# DoorchimeCR2.net
KiCad netlist of a schematic drawn in EAGLE
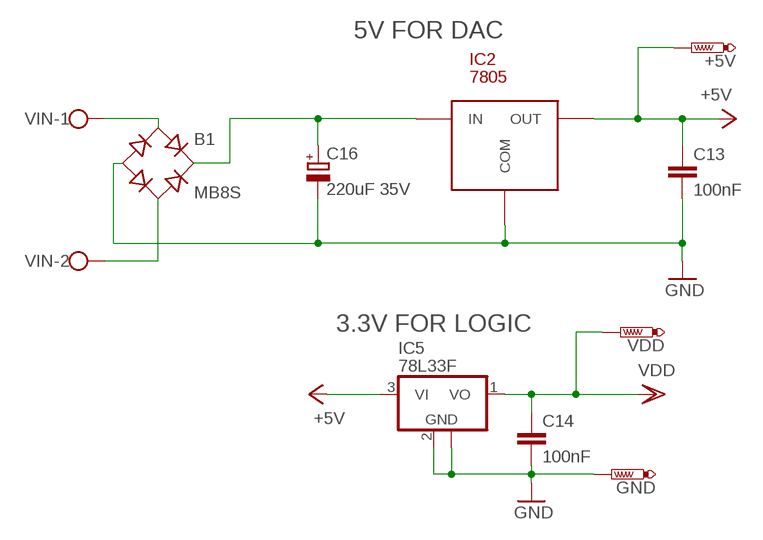
[diagram p0: schematic, sheet 1]
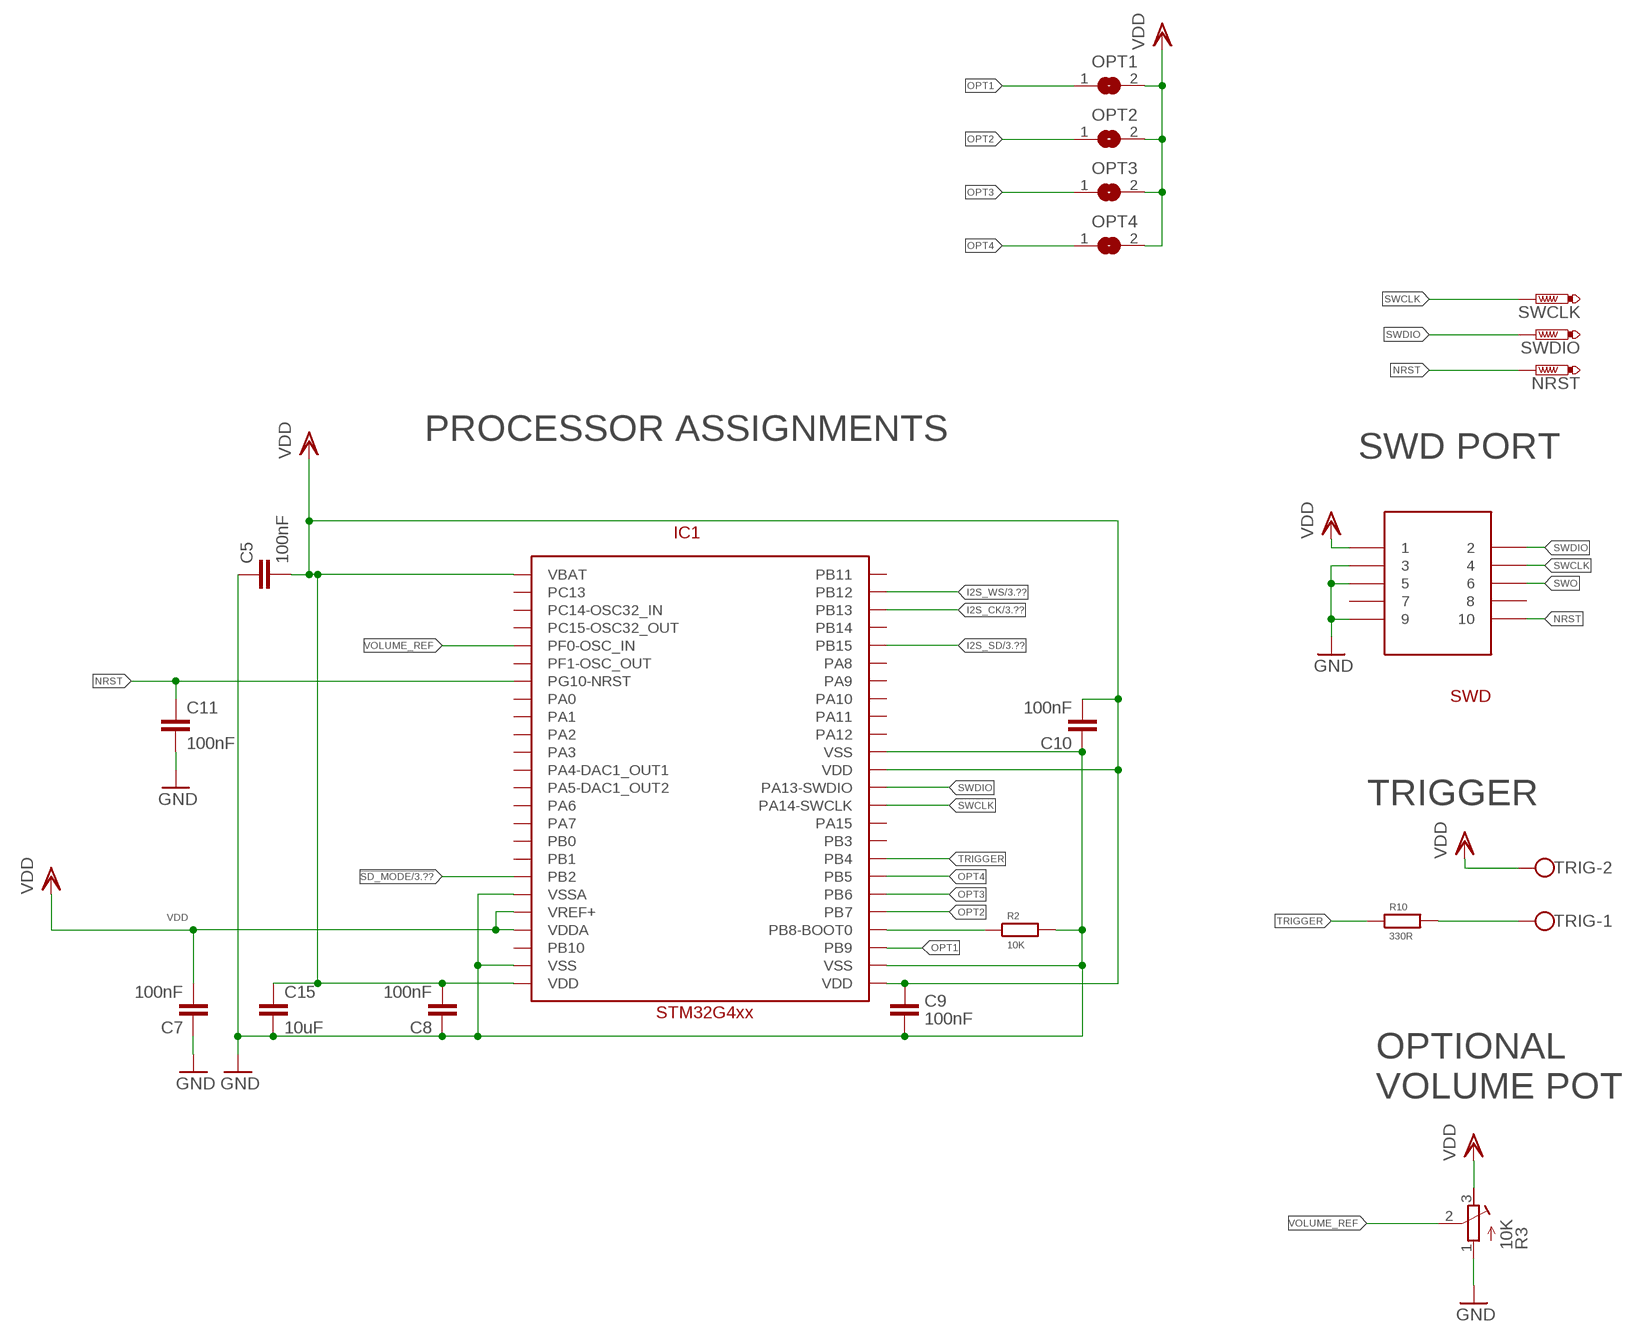
[diagram p1: schematic, sheet 2]
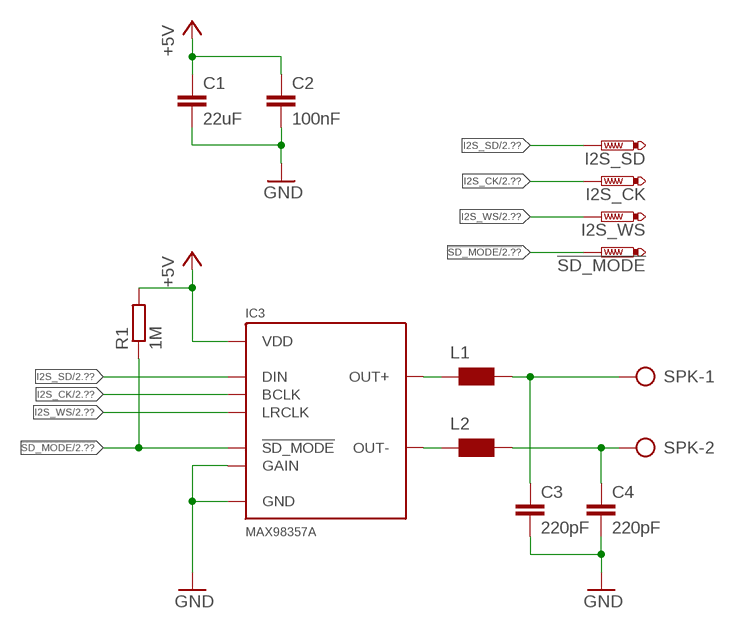
[diagram p2: schematic, sheet 3]

(export (version "E")
  (design (tool "Eeschema 10.0.6"))
  (components
    (comp (ref "+5V")
      (value "PTR1TP15R")
      (footprint "eagle-import:TP15R")
      (libsource (lib "eagle-import") (part "PTR1TP15R"))
    )
    (comp (ref "B1")
      (value "MB8S")
      (footprint "eagle-import:SOIC-4")
      (libsource (lib "eagle-import") (part "MBS8"))
    )
    (comp (ref "C13")
      (value "100nF")
      (footprint "eagle-import:C0603")
      (libsource (lib "eagle-import") (part "C-EUC0603"))
    )
    (comp (ref "C14")
      (value "100nF")
      (footprint "eagle-import:C0603")
      (libsource (lib "eagle-import") (part "C-EUC0603"))
    )
    (comp (ref "C16")
      (value "220uF 35V")
      (footprint "eagle-import:153CLV-0807")
      (libsource (lib "eagle-import") (part "CPOL-EU153CLV-0807"))
    )
    (comp (ref "GND")
      (value "PTR1TP15R")
      (footprint "eagle-import:TP15R")
      (libsource (lib "eagle-import") (part "PTR1TP15R"))
    )
    (comp (ref "IC2")
      (value "7805")
      (footprint "eagle-import:D2PAK")
      (libsource (lib "eagle-import") (part "78XX-D2PAK"))
    )
    (comp (ref "IC5")
      (value "78L33F")
      (footprint "eagle-import:SOT89")
      (libsource (lib "eagle-import") (part "78LF05"))
    )
    (comp (ref "VDD")
      (value "PTR1TP15R")
      (footprint "eagle-import:TP15R")
      (libsource (lib "eagle-import") (part "PTR1TP15R"))
    )
    (comp (ref "VIN")
      (value "W237-102")
      (footprint "eagle-import:W237-102")
      (fields (field (name "MPN") "237-102"))
      (libsource (lib "eagle-import") (part "W237-102"))
    )
    (comp (ref "C5")
      (value "100nF")
      (footprint "eagle-import:C0603")
      (libsource (lib "eagle-import") (part "C-EUC0603"))
    )
    (comp (ref "C7")
      (value "100nF")
      (footprint "eagle-import:C0603")
      (libsource (lib "eagle-import") (part "C-EUC0603"))
    )
    (comp (ref "C8")
      (value "100nF")
      (footprint "eagle-import:C0603")
      (libsource (lib "eagle-import") (part "C-EUC0603"))
    )
    (comp (ref "C9")
      (value "100nF")
      (footprint "eagle-import:C0603")
      (libsource (lib "eagle-import") (part "C-EUC0603"))
    )
    (comp (ref "C10")
      (value "100nF")
      (footprint "eagle-import:C0603")
      (libsource (lib "eagle-import") (part "C-EUC0603"))
    )
    (comp (ref "C11")
      (value "100nF")
      (footprint "eagle-import:C0603")
      (libsource (lib "eagle-import") (part "C-EUC0603"))
    )
    (comp (ref "C15")
      (value "10uF")
      (footprint "eagle-import:C0603")
      (libsource (lib "eagle-import") (part "C-EUC0603"))
    )
    (comp (ref "IC1")
      (value "STM32G4xx")
      (footprint "eagle-import:TQFP48")
      (libsource (lib "eagle-import") (part "STM32G431-C8T6"))
    )
    (comp (ref "NRST")
      (value "PTR1TP15R")
      (footprint "eagle-import:TP15R")
      (libsource (lib "eagle-import") (part "PTR1TP15R"))
    )
    (comp (ref "OPT1")
      (value "SJ")
      (footprint "eagle-import:SJ")
      (libsource (lib "eagle-import") (part "SJ"))
    )
    (comp (ref "OPT2")
      (value "SJ")
      (footprint "eagle-import:SJ")
      (libsource (lib "eagle-import") (part "SJ"))
    )
    (comp (ref "OPT3")
      (value "SJ")
      (footprint "eagle-import:SJ")
      (libsource (lib "eagle-import") (part "SJ"))
    )
    (comp (ref "OPT4")
      (value "SJ")
      (footprint "eagle-import:SJ")
      (libsource (lib "eagle-import") (part "SJ"))
    )
    (comp (ref "R2")
      (value "10K")
      (footprint "eagle-import:R0603")
      (libsource (lib "eagle-import") (part "R-EU_R0603"))
    )
    (comp (ref "R3")
      (value "10K")
      (footprint "eagle-import:RTRIM3339P")
      (libsource (lib "eagle-import") (part "R-TRIMM3339P"))
    )
    (comp (ref "R10")
      (value "330R")
      (footprint "eagle-import:R0603")
      (libsource (lib "eagle-import") (part "R-EU_R0603"))
    )
    (comp (ref "SWCLK")
      (value "PTR1TP15R")
      (footprint "eagle-import:TP15R")
      (libsource (lib "eagle-import") (part "PTR1TP15R"))
    )
    (comp (ref "SWD")
      (value "FTSH-105-01")
      (footprint "eagle-import:FTSH-105-01-XXX-DV-K")
      (libsource (lib "eagle-import") (part "FTSH-105-01"))
    )
    (comp (ref "SWDIO")
      (value "PTR1TP15R")
      (footprint "eagle-import:TP15R")
      (libsource (lib "eagle-import") (part "PTR1TP15R"))
    )
    (comp (ref "TRIG")
      (value "W237-102")
      (footprint "eagle-import:W237-102")
      (fields (field (name "MPN") "237-102"))
      (libsource (lib "eagle-import") (part "W237-102"))
    )
    (comp (ref "!SD_MODE")
      (value "PTR1TP15R")
      (footprint "eagle-import:TP15R")
      (libsource (lib "eagle-import") (part "PTR1TP15R"))
    )
    (comp (ref "C1")
      (value "22uF")
      (footprint "eagle-import:C0603")
      (libsource (lib "eagle-import") (part "C-EUC0603"))
    )
    (comp (ref "C2")
      (value "100nF")
      (footprint "eagle-import:C0603")
      (libsource (lib "eagle-import") (part "C-EUC0603"))
    )
    (comp (ref "C3")
      (value "220pF")
      (footprint "eagle-import:C0603")
      (libsource (lib "eagle-import") (part "C-EUC0603"))
    )
    (comp (ref "C4")
      (value "220pF")
      (footprint "eagle-import:C0603")
      (libsource (lib "eagle-import") (part "C-EUC0603"))
    )
    (comp (ref "I2S_CK")
      (value "PTR1TP15R")
      (footprint "eagle-import:TP15R")
      (libsource (lib "eagle-import") (part "PTR1TP15R"))
    )
    (comp (ref "I2S_SD")
      (value "PTR1TP15R")
      (footprint "eagle-import:TP15R")
      (libsource (lib "eagle-import") (part "PTR1TP15R"))
    )
    (comp (ref "I2S_WS")
      (value "PTR1TP15R")
      (footprint "eagle-import:TP15R")
      (libsource (lib "eagle-import") (part "PTR1TP15R"))
    )
    (comp (ref "IC3")
      (value "MAX98357A")
      (footprint "eagle-import:TQFN-16")
      (libsource (lib "eagle-import") (part "MAX98357A"))
    )
    (comp (ref "L1")
      (value "WE-CBF_0603")
      (footprint "eagle-import:0603")
      (libsource (lib "eagle-import") (part "WE-CBF_0603"))
    )
    (comp (ref "L2")
      (value "WE-CBF_0603")
      (footprint "eagle-import:0603")
      (libsource (lib "eagle-import") (part "WE-CBF_0603"))
    )
    (comp (ref "R1")
      (value "1M")
      (footprint "eagle-import:R0603")
      (libsource (lib "eagle-import") (part "R-EU_R0603"))
    )
    (comp (ref "SPK")
      (value "W237-102")
      (footprint "eagle-import:W237-102")
      (fields (field (name "MPN") "237-102"))
      (libsource (lib "eagle-import") (part "W237-102"))
    )
  )
  (nets
    (net (code "1") (name "+5V") (class "Default")
      (node (ref "+5V") (pin "TP") (pinfunction "TP_TP") (pintype "input"))
      (node (ref "C1") (pin "1") (pinfunction "1_1") (pintype "passive"))
      (node (ref "C13") (pin "1") (pinfunction "1_1") (pintype "passive"))
      (node (ref "C2") (pin "1") (pinfunction "1_1") (pintype "passive"))
      (node (ref "IC2") (pin "OUT") (pinfunction "OUT_OUT") (pintype "bidirectional"))
      (node (ref "IC3") (pin "P$7") (pinfunction "VDD_P$7") (pintype "bidirectional"))
      (node (ref "IC3") (pin "P$8") (pinfunction "VDD_P$8") (pintype "bidirectional"))
      (node (ref "IC5") (pin "3") (pinfunction "VI_3") (pintype "input"))
      (node (ref "R1") (pin "2") (pinfunction "2_2") (pintype "passive"))
    )
    (net (code "2") (name "GND") (class "Default")
      (node (ref "B1") (pin "-") (pinfunction "-_-") (pintype "passive"))
      (node (ref "C1") (pin "2") (pinfunction "2_2") (pintype "passive"))
      (node (ref "C10") (pin "1") (pinfunction "1_1") (pintype "passive"))
      (node (ref "C11") (pin "2") (pinfunction "2_2") (pintype "passive"))
      (node (ref "C13") (pin "2") (pinfunction "2_2") (pintype "passive"))
      (node (ref "C14") (pin "2") (pinfunction "2_2") (pintype "passive"))
      (node (ref "C15") (pin "2") (pinfunction "2_2") (pintype "passive"))
      (node (ref "C16") (pin "-") (pinfunction "-_-") (pintype "passive"))
      (node (ref "C2") (pin "2") (pinfunction "2_2") (pintype "passive"))
      (node (ref "C3") (pin "2") (pinfunction "2_2") (pintype "passive"))
      (node (ref "C4") (pin "2") (pinfunction "2_2") (pintype "passive"))
      (node (ref "C5") (pin "1") (pinfunction "1_1") (pintype "passive"))
      (node (ref "C7") (pin "1") (pinfunction "1_1") (pintype "passive"))
      (node (ref "C8") (pin "1") (pinfunction "1_1") (pintype "passive"))
      (node (ref "C9") (pin "1") (pinfunction "1_1") (pintype "passive"))
      (node (ref "GND") (pin "TP") (pinfunction "TP_TP") (pintype "input"))
      (node (ref "IC1") (pin "VSS@23") (pinfunction "VSS_VSS@23") (pintype "power_in"))
      (node (ref "IC1") (pin "VSS@35") (pinfunction "VSS_VSS@35") (pintype "power_in"))
      (node (ref "IC1") (pin "VSS@47") (pinfunction "VSS_VSS@47") (pintype "power_in"))
      (node (ref "IC1") (pin "VSSA") (pinfunction "VSSA_VSSA") (pintype "power_in"))
      (node (ref "IC2") (pin "COM") (pinfunction "COM_COM") (pintype "bidirectional"))
      (node (ref "IC3") (pin "P$11") (pinfunction "GND_P$11") (pintype "bidirectional"))
      (node (ref "IC3") (pin "P$15") (pinfunction "GND_P$15") (pintype "bidirectional"))
      (node (ref "IC3") (pin "P$2") (pinfunction "GAIN_P$2") (pintype "bidirectional"))
      (node (ref "IC3") (pin "P$3") (pinfunction "GND_P$3") (pintype "bidirectional"))
      (node (ref "IC3") (pin "P$EP") (pinfunction "GND_P$EP") (pintype "bidirectional"))
      (node (ref "IC5") (pin "2") (pinfunction "GND_2") (pintype "passive"))
      (node (ref "IC5") (pin "2@1") (pinfunction "GND_2@1") (pintype "passive"))
      (node (ref "R2") (pin "2") (pinfunction "2_2") (pintype "passive"))
      (node (ref "R3") (pin "1") (pinfunction "E_1") (pintype "passive"))
      (node (ref "SWD") (pin "3") (pinfunction "3_3") (pintype "passive"))
      (node (ref "SWD") (pin "5") (pinfunction "5_5") (pintype "passive"))
      (node (ref "SWD") (pin "9") (pinfunction "9_9") (pintype "passive"))
    )
    (net (code "3") (name "I2S_CK") (class "Default")
      (node (ref "I2S_CK") (pin "TP") (pinfunction "TP_TP") (pintype "input"))
      (node (ref "IC1") (pin "PB13") (pinfunction "PB13_PB13") (pintype "bidirectional"))
      (node (ref "IC3") (pin "P$16") (pinfunction "BCLK_P$16") (pintype "bidirectional"))
    )
    (net (code "4") (name "I2S_SD") (class "Default")
      (node (ref "I2S_SD") (pin "TP") (pinfunction "TP_TP") (pintype "input"))
      (node (ref "IC1") (pin "PB15") (pinfunction "PB15_PB15") (pintype "bidirectional"))
      (node (ref "IC3") (pin "P$1") (pinfunction "DIN_P$1") (pintype "bidirectional"))
    )
    (net (code "5") (name "I2S_WS") (class "Default")
      (node (ref "I2S_WS") (pin "TP") (pinfunction "TP_TP") (pintype "input"))
      (node (ref "IC1") (pin "PB12") (pinfunction "PB12_PB12") (pintype "bidirectional"))
      (node (ref "IC3") (pin "P$14") (pinfunction "LRCLK_P$14") (pintype "bidirectional"))
    )
    (net (code "6") (name "NRST") (class "Default")
      (node (ref "C11") (pin "1") (pinfunction "1_1") (pintype "passive"))
      (node (ref "IC1") (pin "PG10-NRST") (pinfunction "PG10-NRST_PG10-NRST") (pintype "bidirectional"))
      (node (ref "NRST") (pin "TP") (pinfunction "TP_TP") (pintype "input"))
      (node (ref "SWD") (pin "10") (pinfunction "10_10") (pintype "passive"))
    )
    (net (code "7") (name "Net-(B1-AC1)") (class "Default")
      (node (ref "B1") (pin "~1") (pinfunction "AC1_~1") (pintype "passive"))
      (node (ref "VIN") (pin "1") (pinfunction "KL_1") (pintype "passive"))
    )
    (net (code "8") (name "Net-(B1-AC2)") (class "Default")
      (node (ref "B1") (pin "~2") (pinfunction "AC2_~2") (pintype "passive"))
      (node (ref "VIN") (pin "2") (pinfunction "KL_2") (pintype "passive"))
    )
    (net (code "9") (name "Net-(B1-Pad+)") (class "Default")
      (node (ref "B1") (pin "+") (pinfunction "+_+") (pintype "passive"))
      (node (ref "C16") (pin "+") (pinfunction "+_+") (pintype "passive"))
      (node (ref "IC2") (pin "IN") (pinfunction "IN_IN") (pintype "bidirectional"))
    )
    (net (code "10") (name "Net-(IC1-PadPB8-BOOT0)") (class "Default")
      (node (ref "IC1") (pin "PB8-BOOT0") (pinfunction "PB8-BOOT0_PB8-BOOT0") (pintype "bidirectional"))
      (node (ref "R2") (pin "1") (pinfunction "1_1") (pintype "passive"))
    )
    (net (code "11") (name "Net-(IC3-OUT+)") (class "Default")
      (node (ref "IC3") (pin "P$9") (pinfunction "OUT+_P$9") (pintype "bidirectional"))
      (node (ref "L1") (pin "1") (pinfunction "1_1") (pintype "passive"))
    )
    (net (code "12") (name "Net-(IC3-OUT-)") (class "Default")
      (node (ref "IC3") (pin "P$10") (pinfunction "OUT-_P$10") (pintype "bidirectional"))
      (node (ref "L2") (pin "1") (pinfunction "1_1") (pintype "passive"))
    )
    (net (code "13") (name "Net-(SPKA-KL)") (class "Default")
      (node (ref "C3") (pin "1") (pinfunction "1_1") (pintype "passive"))
      (node (ref "L1") (pin "2") (pinfunction "2_2") (pintype "passive"))
      (node (ref "SPK") (pin "1") (pinfunction "KL_1") (pintype "passive"))
    )
    (net (code "14") (name "Net-(SPKB-KL)") (class "Default")
      (node (ref "C4") (pin "1") (pinfunction "1_1") (pintype "passive"))
      (node (ref "L2") (pin "2") (pinfunction "2_2") (pintype "passive"))
      (node (ref "SPK") (pin "2") (pinfunction "KL_2") (pintype "passive"))
    )
    (net (code "15") (name "Net-(TRIGA-KL)") (class "Default")
      (node (ref "R10") (pin "2") (pinfunction "2_2") (pintype "passive"))
      (node (ref "TRIG") (pin "1") (pinfunction "KL_1") (pintype "passive"))
    )
    (net (code "16") (name "OPT1") (class "Default")
      (node (ref "IC1") (pin "PB9") (pinfunction "PB9_PB9") (pintype "bidirectional"))
      (node (ref "OPT1") (pin "1") (pinfunction "1_1") (pintype "passive"))
    )
    (net (code "17") (name "OPT2") (class "Default")
      (node (ref "IC1") (pin "PB7") (pinfunction "PB7_PB7") (pintype "bidirectional"))
      (node (ref "OPT2") (pin "1") (pinfunction "1_1") (pintype "passive"))
    )
    (net (code "18") (name "OPT3") (class "Default")
      (node (ref "IC1") (pin "PB6") (pinfunction "PB6_PB6") (pintype "bidirectional"))
      (node (ref "OPT3") (pin "1") (pinfunction "1_1") (pintype "passive"))
    )
    (net (code "19") (name "OPT4") (class "Default")
      (node (ref "IC1") (pin "PB5") (pinfunction "PB5_PB5") (pintype "bidirectional"))
      (node (ref "OPT4") (pin "1") (pinfunction "1_1") (pintype "passive"))
    )
    (net (code "20") (name "SWCLK") (class "Default")
      (node (ref "IC1") (pin "PA14-SWCLK") (pinfunction "PA14-SWCLK_PA14-SWCLK") (pintype "bidirectional"))
      (node (ref "SWCLK") (pin "TP") (pinfunction "TP_TP") (pintype "input"))
      (node (ref "SWD") (pin "4") (pinfunction "4_4") (pintype "passive"))
    )
    (net (code "21") (name "SWDIO") (class "Default")
      (node (ref "IC1") (pin "PA13-SWDIO") (pinfunction "PA13-SWDIO_PA13-SWDIO") (pintype "bidirectional"))
      (node (ref "SWD") (pin "2") (pinfunction "2_2") (pintype "passive"))
      (node (ref "SWDIO") (pin "TP") (pinfunction "TP_TP") (pintype "input"))
    )
    (net (code "22") (name "SWO") (class "Default")
      (node (ref "SWD") (pin "6") (pinfunction "6_6") (pintype "passive"))
    )
    (net (code "23") (name "TRIGGER") (class "Default")
      (node (ref "IC1") (pin "PB4") (pinfunction "PB4_PB4") (pintype "bidirectional"))
      (node (ref "R10") (pin "1") (pinfunction "1_1") (pintype "passive"))
    )
    (net (code "24") (name "VDD") (class "Default")
      (node (ref "C10") (pin "2") (pinfunction "2_2") (pintype "passive"))
      (node (ref "C14") (pin "1") (pinfunction "1_1") (pintype "passive"))
      (node (ref "C15") (pin "1") (pinfunction "1_1") (pintype "passive"))
      (node (ref "C5") (pin "2") (pinfunction "2_2") (pintype "passive"))
      (node (ref "C7") (pin "2") (pinfunction "2_2") (pintype "passive"))
      (node (ref "C8") (pin "2") (pinfunction "2_2") (pintype "passive"))
      (node (ref "C9") (pin "2") (pinfunction "2_2") (pintype "passive"))
      (node (ref "IC1") (pin "VBAT") (pinfunction "VBAT_VBAT") (pintype "power_in"))
      (node (ref "IC1") (pin "VDD@24") (pinfunction "VDD_VDD@24") (pintype "power_in"))
      (node (ref "IC1") (pin "VDD@36") (pinfunction "VDD_VDD@36") (pintype "power_in"))
      (node (ref "IC1") (pin "VDD@48") (pinfunction "VDD_VDD@48") (pintype "power_in"))
      (node (ref "IC1") (pin "VDDA") (pinfunction "VDDA_VDDA") (pintype "power_in"))
      (node (ref "IC1") (pin "VREF+") (pinfunction "VREF+_VREF+") (pintype "power_in"))
      (node (ref "IC5") (pin "1") (pinfunction "VO_1") (pintype "passive"))
      (node (ref "OPT1") (pin "2") (pinfunction "2_2") (pintype "passive"))
      (node (ref "OPT2") (pin "2") (pinfunction "2_2") (pintype "passive"))
      (node (ref "OPT3") (pin "2") (pinfunction "2_2") (pintype "passive"))
      (node (ref "OPT4") (pin "2") (pinfunction "2_2") (pintype "passive"))
      (node (ref "R3") (pin "3") (pinfunction "A_3") (pintype "passive"))
      (node (ref "SWD") (pin "1") (pinfunction "1_1") (pintype "passive"))
      (node (ref "TRIG") (pin "2") (pinfunction "KL_2") (pintype "passive"))
      (node (ref "VDD") (pin "TP") (pinfunction "TP_TP") (pintype "input"))
    )
    (net (code "25") (name "VOLUME_REF") (class "Default")
      (node (ref "IC1") (pin "PF0-OSC_IN") (pinfunction "PF0-OSC_IN_PF0-OSC_IN") (pintype "bidirectional"))
      (node (ref "R3") (pin "2") (pinfunction "S_2") (pintype "passive"))
    )
    (net (code "26") (name "unconnected-(IC1-PadPA0)") (class "Default")
      (node (ref "IC1") (pin "PA0") (pinfunction "PA0_PA0") (pintype "bidirectional"))
    )
    (net (code "27") (name "unconnected-(IC1-PadPA1)") (class "Default")
      (node (ref "IC1") (pin "PA1") (pinfunction "PA1_PA1") (pintype "bidirectional"))
    )
    (net (code "28") (name "unconnected-(IC1-PadPA2)") (class "Default")
      (node (ref "IC1") (pin "PA2") (pinfunction "PA2_PA2") (pintype "bidirectional"))
    )
    (net (code "29") (name "unconnected-(IC1-PadPA3)") (class "Default")
      (node (ref "IC1") (pin "PA3") (pinfunction "PA3_PA3") (pintype "bidirectional"))
    )
    (net (code "30") (name "unconnected-(IC1-PadPA4-DAC1_OUT1)") (class "Default")
      (node (ref "IC1") (pin "PA4-DAC1_OUT1") (pinfunction "PA4-DAC1_OUT1_PA4-DAC1_OUT1") (pintype "bidirectional"))
    )
    (net (code "31") (name "unconnected-(IC1-PadPA5-DAC1_OUT2)") (class "Default")
      (node (ref "IC1") (pin "PA5-DAC1_OUT2") (pinfunction "PA5-DAC1_OUT2_PA5-DAC1_OUT2") (pintype "bidirectional"))
    )
    (net (code "32") (name "unconnected-(IC1-PadPA6)") (class "Default")
      (node (ref "IC1") (pin "PA6") (pinfunction "PA6_PA6") (pintype "bidirectional"))
    )
    (net (code "33") (name "unconnected-(IC1-PadPA7)") (class "Default")
      (node (ref "IC1") (pin "PA7") (pinfunction "PA7_PA7") (pintype "bidirectional"))
    )
    (net (code "34") (name "unconnected-(IC1-PadPA8)") (class "Default")
      (node (ref "IC1") (pin "PA8") (pinfunction "PA8_PA8") (pintype "bidirectional"))
    )
    (net (code "35") (name "unconnected-(IC1-PadPA9)") (class "Default")
      (node (ref "IC1") (pin "PA9") (pinfunction "PA9_PA9") (pintype "bidirectional"))
    )
    (net (code "36") (name "unconnected-(IC1-PadPA10)") (class "Default")
      (node (ref "IC1") (pin "PA10") (pinfunction "PA10_PA10") (pintype "bidirectional"))
    )
    (net (code "37") (name "unconnected-(IC1-PadPA11)") (class "Default")
      (node (ref "IC1") (pin "PA11") (pinfunction "PA11_PA11") (pintype "bidirectional"))
    )
    (net (code "38") (name "unconnected-(IC1-PadPA12)") (class "Default")
      (node (ref "IC1") (pin "PA12") (pinfunction "PA12_PA12") (pintype "bidirectional"))
    )
    (net (code "39") (name "unconnected-(IC1-PadPA15)") (class "Default")
      (node (ref "IC1") (pin "PA15") (pinfunction "PA15_PA15") (pintype "bidirectional"))
    )
    (net (code "40") (name "unconnected-(IC1-PadPB0)") (class "Default")
      (node (ref "IC1") (pin "PB0") (pinfunction "PB0_PB0") (pintype "bidirectional"))
    )
    (net (code "41") (name "unconnected-(IC1-PadPB1)") (class "Default")
      (node (ref "IC1") (pin "PB1") (pinfunction "PB1_PB1") (pintype "bidirectional"))
    )
    (net (code "42") (name "unconnected-(IC1-PadPB3)") (class "Default")
      (node (ref "IC1") (pin "PB3") (pinfunction "PB3_PB3") (pintype "bidirectional"))
    )
    (net (code "43") (name "unconnected-(IC1-PadPB10)") (class "Default")
      (node (ref "IC1") (pin "PB10") (pinfunction "PB10_PB10") (pintype "bidirectional"))
    )
    (net (code "44") (name "unconnected-(IC1-PadPB11)") (class "Default")
      (node (ref "IC1") (pin "PB11") (pinfunction "PB11_PB11") (pintype "bidirectional"))
    )
    (net (code "45") (name "unconnected-(IC1-PadPB14)") (class "Default")
      (node (ref "IC1") (pin "PB14") (pinfunction "PB14_PB14") (pintype "bidirectional"))
    )
    (net (code "46") (name "unconnected-(IC1-PadPC13)") (class "Default")
      (node (ref "IC1") (pin "PC13") (pinfunction "PC13_PC13") (pintype "bidirectional"))
    )
    (net (code "47") (name "unconnected-(IC1-PadPC14-OSC32_IN)") (class "Default")
      (node (ref "IC1") (pin "PC14-OSC32_IN") (pinfunction "PC14-OSC32_IN_PC14-OSC32_IN") (pintype "bidirectional"))
    )
    (net (code "48") (name "unconnected-(IC1-PadPC15-OSC32_OUT)") (class "Default")
      (node (ref "IC1") (pin "PC15-OSC32_OUT") (pinfunction "PC15-OSC32_OUT_PC15-OSC32_OUT") (pintype "bidirectional"))
    )
    (net (code "49") (name "unconnected-(IC1-PadPF1-OSC_OUT)") (class "Default")
      (node (ref "IC1") (pin "PF1-OSC_OUT") (pinfunction "PF1-OSC_OUT_PF1-OSC_OUT") (pintype "bidirectional"))
    )
    (net (code "50") (name "unconnected-(SWD-Pad7)") (class "Default")
      (node (ref "SWD") (pin "7") (pinfunction "7_7") (pintype "passive"))
    )
    (net (code "51") (name "unconnected-(SWD-Pad8)") (class "Default")
      (node (ref "SWD") (pin "8") (pinfunction "8_8") (pintype "passive"))
    )
    (net (code "52") (name "~{SD_MODE}") (class "Default")
      (node (ref "!SD_MODE") (pin "TP") (pinfunction "TP_TP") (pintype "input"))
      (node (ref "IC1") (pin "PB2") (pinfunction "PB2_PB2") (pintype "bidirectional"))
      (node (ref "IC3") (pin "P$4") (pinfunction "~{SD_MODE}_P$4") (pintype "bidirectional"))
      (node (ref "R1") (pin "1") (pinfunction "1_1") (pintype "passive"))
    )
  )
)
